# pidp11-io-expander.net
KiCad netlist of a schematic drawn in Altium Designer
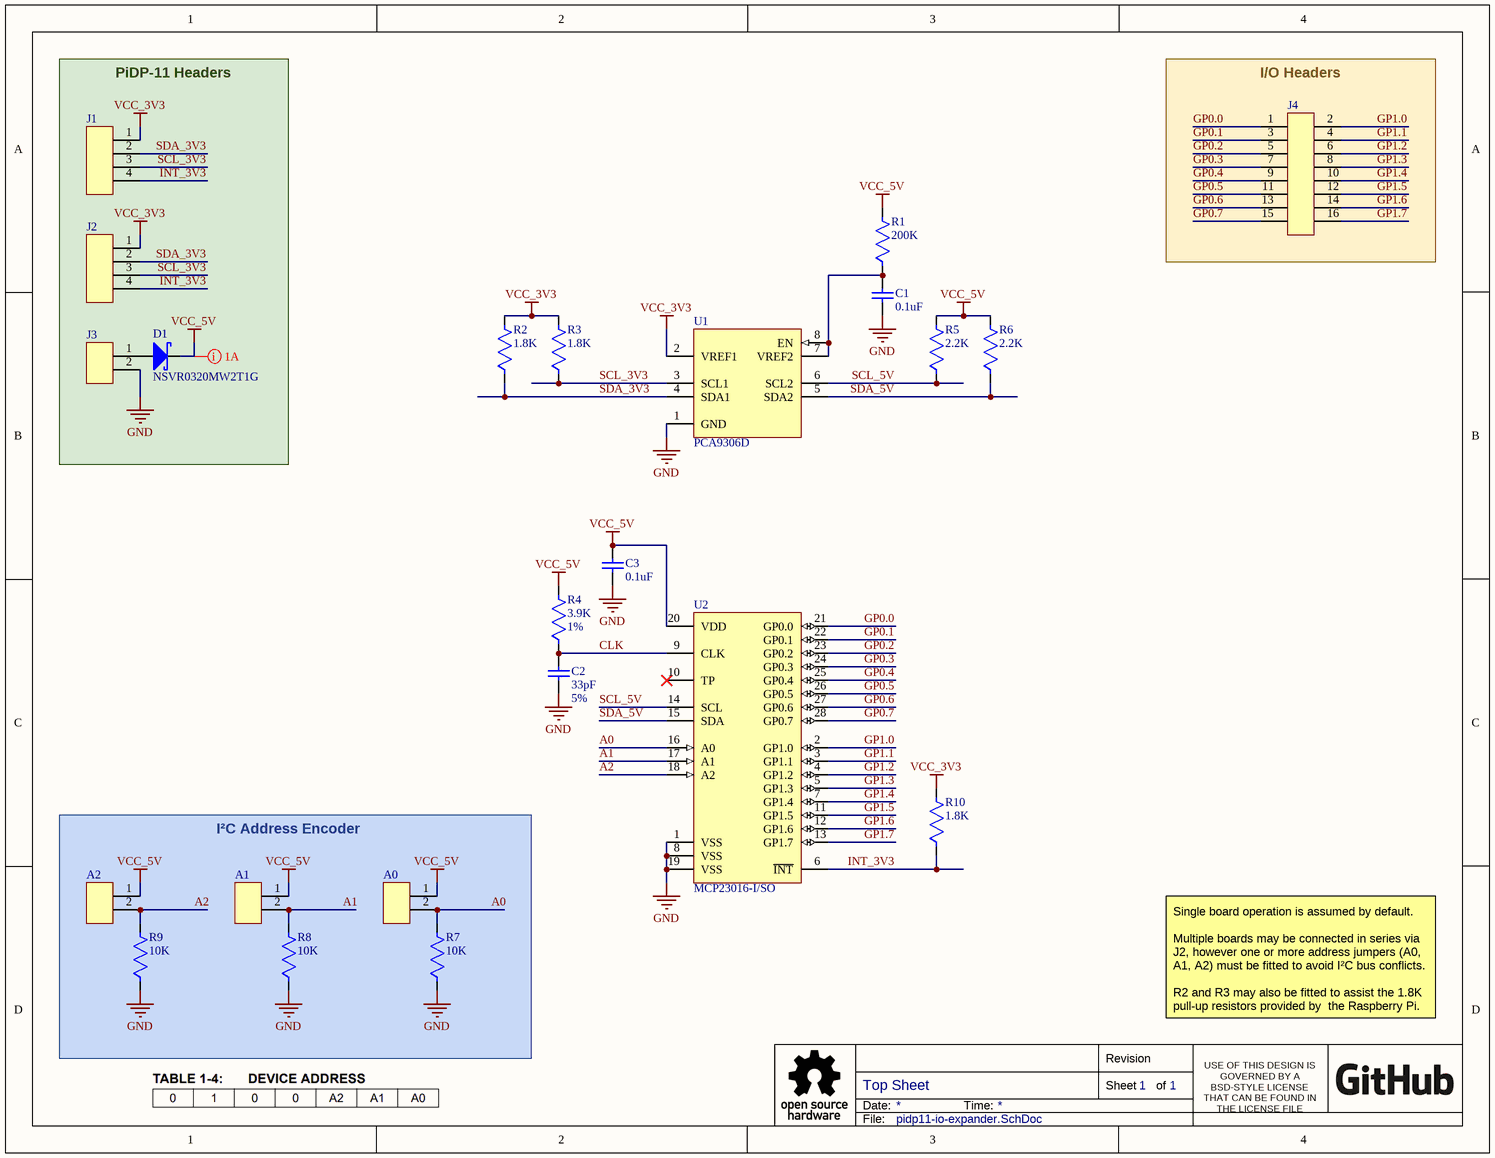
[diagram p0: pidp11-io-expander.SchDoc]

(export (version "E")
  (design (tool "Eeschema 10.0.6"))
  (components
    (comp (ref "A0")
      (value "10129378-902001BLF")
      (footprint "AMPH-10129378-902001BLF")
      (description "CONN HEADER VERT 2POS 2.54MM")
      (fields (field (name "MANUFACTURER") "Amphenol ICC"))
      (libsource (lib "Unified Components") (part "10129378-902001BLF"))
    )
    (comp (ref "A1")
      (value "10129378-902001BLF")
      (footprint "AMPH-10129378-902001BLF")
      (description "CONN HEADER VERT 2POS 2.54MM")
      (fields (field (name "MANUFACTURER") "Amphenol ICC"))
      (libsource (lib "Unified Components") (part "10129378-902001BLF"))
    )
    (comp (ref "A2")
      (value "10129378-902001BLF")
      (footprint "AMPH-10129378-902001BLF")
      (description "CONN HEADER VERT 2POS 2.54MM")
      (fields (field (name "MANUFACTURER") "Amphenol ICC"))
      (libsource (lib "Unified Components") (part "10129378-902001BLF"))
    )
    (comp (ref "C1")
      (value "0.1uF")
      (footprint "AVX-CC0402")
      (description "CAP CER 0.1UF 25V X7R 0402")
      (fields (field (name "MANUFACTURER PART NUMBER") "04023C104KAT2A") (field (name "MANUFACTURER") "AVX"))
      (libsource (lib "Unified Components") (part "04023C104KAT2A"))
    )
    (comp (ref "C2")
      (value "33pF")
      (footprint "AVX-CC0402")
      (description "CAP CER 33PF 25V C0G/NP0 0402")
      (fields
        (field (name "MANUFACTURER PART NUMBER") "04023A330JAT2A")
        (field (name "MANUFACTURER") "AVX")
        (field (name "TOLERANCE") "5%")
      )
      (libsource (lib "Unified Components") (part "04023A330JAT2A"))
    )
    (comp (ref "C3")
      (value "0.1uF")
      (footprint "AVX-CC0402")
      (description "CAP CER 0.1UF 25V X7R 0402")
      (fields (field (name "MANUFACTURER PART NUMBER") "04023C104KAT2A") (field (name "MANUFACTURER") "AVX"))
      (libsource (lib "Unified Components") (part "04023C104KAT2A"))
    )
    (comp (ref "D1")
      (value "NSVR0320MW2T1G")
      (footprint "ONSC-NSVR0320MW2T1G")
      (description "DIODE SCHOTTKY 20V 1A SOD323")
      (fields (field (name "MANUFACTURER") "ON Semiconductor"))
      (libsource (lib "Unified Components") (part "NSVR0320MW2T1G"))
    )
    (comp (ref "J1")
      (value "10129378-904001BLF")
      (footprint "AMPH-10129378-904001BLF")
      (description "CONN HEADER VERT 4POS 2.54MM")
      (fields (field (name "MANUFACTURER") "Amphenol ICC"))
      (libsource (lib "Unified Components") (part "10129378-904001BLF"))
    )
    (comp (ref "J2")
      (value "10129378-904001BLF")
      (footprint "AMPH-10129378-904001BLF")
      (description "CONN HEADER VERT 4POS 2.54MM")
      (fields (field (name "MANUFACTURER") "Amphenol ICC"))
      (libsource (lib "Unified Components") (part "10129378-904001BLF"))
    )
    (comp (ref "J3")
      (value "10129378-902001BLF")
      (footprint "AMPH-10129378-902001BLF")
      (description "CONN HEADER VERT 2POS 2.54MM")
      (fields (field (name "MANUFACTURER") "Amphenol ICC"))
      (libsource (lib "Unified Components") (part "10129378-902001BLF"))
    )
    (comp (ref "J4")
      (value "10129381-916001BLF")
      (footprint "AMPH-10129381-916001BLF")
      (description "CONN HEADER VERT 16POS 2.54MM")
      (fields (field (name "MANUFACTURER") "Amphenol ICC"))
      (libsource (lib "Unified Components") (part "10129381-916001BLF"))
    )
    (comp (ref "R1")
      (value "200K")
      (footprint "VBEY-CR0402")
      (description "RES SMD 200K OHM 1% 1/10W 0402")
      (fields
        (field (name "MANUFACTURER") "Vishay Beyschlag")
        (field (name "MANUFACTURER PART NUMBER") "MCS04020C2003FE000")
      )
      (libsource (lib "Unified Components") (part "MCS04020C2003FE000"))
    )
    (comp (ref "R2")
      (value "1.8K")
      (footprint "VBEY-CR0402")
      (description "RES SMD 1.8K OHM 1% 1/10W 0402")
      (fields
        (field (name "MANUFACTURER") "Vishay Beyschlag")
        (field (name "MANUFACTURER PART NUMBER") "MCS04020C1801FE000")
      )
      (libsource (lib "Unified Components") (part "MCS04020C1801FE000"))
    )
    (comp (ref "R3")
      (value "1.8K")
      (footprint "VBEY-CR0402")
      (description "RES SMD 1.8K OHM 1% 1/10W 0402")
      (fields
        (field (name "MANUFACTURER") "Vishay Beyschlag")
        (field (name "MANUFACTURER PART NUMBER") "MCS04020C1801FE000")
      )
      (libsource (lib "Unified Components") (part "MCS04020C1801FE000"))
    )
    (comp (ref "R4")
      (value "3.9K")
      (footprint "VBEY-CR0402")
      (description "RES SMD 3.9K OHM 1% 1/10W 0402")
      (fields
        (field (name "MANUFACTURER") "Vishay Beyschlag")
        (field (name "MANUFACTURER PART NUMBER") "MCS04020C3901FE000")
        (field (name "TOLERANCE") "1%")
      )
      (libsource (lib "Unified Components") (part "MCS04020C3901FE000"))
    )
    (comp (ref "R5")
      (value "2.2K")
      (footprint "VBEY-CR0402")
      (description "RES SMD 2.2K OHM 1% 1/10W 0402")
      (fields
        (field (name "MANUFACTURER") "Vishay Beyschlag")
        (field (name "MANUFACTURER PART NUMBER") "MCS04020C2201FE000")
      )
      (libsource (lib "Unified Components") (part "MCS04020C2201FE000"))
    )
    (comp (ref "R6")
      (value "2.2K")
      (footprint "VBEY-CR0402")
      (description "RES SMD 2.2K OHM 1% 1/10W 0402")
      (fields
        (field (name "MANUFACTURER") "Vishay Beyschlag")
        (field (name "MANUFACTURER PART NUMBER") "MCS04020C2201FE000")
      )
      (libsource (lib "Unified Components") (part "MCS04020C2201FE000"))
    )
    (comp (ref "R7")
      (value "10K")
      (footprint "VBEY-CR0402")
      (description "RES SMD 10K OHM 1% 1/10W 0402")
      (fields
        (field (name "MANUFACTURER") "Vishay Beyschlag")
        (field (name "MANUFACTURER PART NUMBER") "MCS0402MC1002FE000")
      )
      (libsource (lib "Unified Components") (part "MCS0402MC1002FE000"))
    )
    (comp (ref "R8")
      (value "10K")
      (footprint "VBEY-CR0402")
      (description "RES SMD 10K OHM 1% 1/10W 0402")
      (fields
        (field (name "MANUFACTURER") "Vishay Beyschlag")
        (field (name "MANUFACTURER PART NUMBER") "MCS0402MC1002FE000")
      )
      (libsource (lib "Unified Components") (part "MCS0402MC1002FE000"))
    )
    (comp (ref "R9")
      (value "10K")
      (footprint "VBEY-CR0402")
      (description "RES SMD 10K OHM 1% 1/10W 0402")
      (fields
        (field (name "MANUFACTURER") "Vishay Beyschlag")
        (field (name "MANUFACTURER PART NUMBER") "MCS0402MC1002FE000")
      )
      (libsource (lib "Unified Components") (part "MCS0402MC1002FE000"))
    )
    (comp (ref "R10")
      (value "1.8K")
      (footprint "VBEY-CR0402")
      (description "RES SMD 1.8K OHM 1% 1/10W 0402")
      (fields
        (field (name "MANUFACTURER") "Vishay Beyschlag")
        (field (name "MANUFACTURER PART NUMBER") "MCS04020C1801FE000")
      )
      (libsource (lib "Unified Components") (part "MCS04020C1801FE000"))
    )
    (comp (ref "U1")
      (value "PCA9306D")
      (footprint "NXP-PCA9306D")
      (description "IC TRNSLTR BIDIRECTIONAL 8SO")
      (fields (field (name "MANUFACTURER") "NXP"))
      (libsource (lib "Unified Components") (part "PCA9306D"))
    )
    (comp (ref "U2")
      (value "MCP23016-I/SO")
      (footprint "MCHP-SOIC-28")
      (description "IC I/O EXPANDER I2C 16B 28SOIC")
      (fields (field (name "MANUFACTURER") "Microchip"))
      (libsource (lib "Unified Components") (part "MCP23016-I/SO"))
    )
  )
  (nets
    (net (code "1") (name "/A0") (class "Default")
      (node (ref "A0") (pin "2") (pintype "open_emitter"))
      (node (ref "R7") (pin "2") (pinfunction "2_2") (pintype "passive"))
      (node (ref "U2") (pin "16") (pinfunction "A0_16") (pintype "input"))
    )
    (net (code "2") (name "/A1") (class "Default")
      (node (ref "A1") (pin "2") (pintype "open_emitter"))
      (node (ref "R8") (pin "2") (pinfunction "2_2") (pintype "passive"))
      (node (ref "U2") (pin "17") (pinfunction "A1_17") (pintype "input"))
    )
    (net (code "3") (name "/A2") (class "Default")
      (node (ref "A2") (pin "2") (pintype "open_emitter"))
      (node (ref "R9") (pin "2") (pinfunction "2_2") (pintype "passive"))
      (node (ref "U2") (pin "18") (pinfunction "A2_18") (pintype "input"))
    )
    (net (code "4") (name "/CLK") (class "Default")
      (node (ref "C2") (pin "1") (pinfunction "1_1") (pintype "passive"))
      (node (ref "R4") (pin "1") (pinfunction "1_1") (pintype "passive"))
      (node (ref "U2") (pin "9") (pinfunction "CLK_9") (pintype "passive"))
    )
    (net (code "5") (name "/GP0.0") (class "Default")
      (node (ref "J4") (pin "1") (pintype "passive"))
      (node (ref "U2") (pin "21") (pinfunction "GP0.0_21") (pintype "bidirectional"))
    )
    (net (code "6") (name "/GP0.1") (class "Default")
      (node (ref "J4") (pin "3") (pintype "passive"))
      (node (ref "U2") (pin "22") (pinfunction "GP0.1_22") (pintype "bidirectional"))
    )
    (net (code "7") (name "/GP0.2") (class "Default")
      (node (ref "J4") (pin "5") (pintype "passive"))
      (node (ref "U2") (pin "23") (pinfunction "GP0.2_23") (pintype "bidirectional"))
    )
    (net (code "8") (name "/GP0.3") (class "Default")
      (node (ref "J4") (pin "7") (pintype "passive"))
      (node (ref "U2") (pin "24") (pinfunction "GP0.3_24") (pintype "bidirectional"))
    )
    (net (code "9") (name "/GP0.4") (class "Default")
      (node (ref "J4") (pin "9") (pintype "passive"))
      (node (ref "U2") (pin "25") (pinfunction "GP0.4_25") (pintype "bidirectional"))
    )
    (net (code "10") (name "/GP0.5") (class "Default")
      (node (ref "J4") (pin "11") (pintype "passive"))
      (node (ref "U2") (pin "26") (pinfunction "GP0.5_26") (pintype "bidirectional"))
    )
    (net (code "11") (name "/GP0.6") (class "Default")
      (node (ref "J4") (pin "13") (pintype "passive"))
      (node (ref "U2") (pin "27") (pinfunction "GP0.6_27") (pintype "bidirectional"))
    )
    (net (code "12") (name "/GP0.7") (class "Default")
      (node (ref "J4") (pin "15") (pintype "passive"))
      (node (ref "U2") (pin "28") (pinfunction "GP0.7_28") (pintype "bidirectional"))
    )
    (net (code "13") (name "/GP1.0") (class "Default")
      (node (ref "J4") (pin "2") (pintype "passive"))
      (node (ref "U2") (pin "2") (pinfunction "GP1.0_2") (pintype "bidirectional"))
    )
    (net (code "14") (name "/GP1.1") (class "Default")
      (node (ref "J4") (pin "4") (pintype "passive"))
      (node (ref "U2") (pin "3") (pinfunction "GP1.1_3") (pintype "bidirectional"))
    )
    (net (code "15") (name "/GP1.2") (class "Default")
      (node (ref "J4") (pin "6") (pintype "passive"))
      (node (ref "U2") (pin "4") (pinfunction "GP1.2_4") (pintype "bidirectional"))
    )
    (net (code "16") (name "/GP1.3") (class "Default")
      (node (ref "J4") (pin "8") (pintype "passive"))
      (node (ref "U2") (pin "5") (pinfunction "GP1.3_5") (pintype "bidirectional"))
    )
    (net (code "17") (name "/GP1.4") (class "Default")
      (node (ref "J4") (pin "10") (pintype "passive"))
      (node (ref "U2") (pin "7") (pinfunction "GP1.4_7") (pintype "bidirectional"))
    )
    (net (code "18") (name "/GP1.5") (class "Default")
      (node (ref "J4") (pin "12") (pintype "passive"))
      (node (ref "U2") (pin "11") (pinfunction "GP1.5_11") (pintype "bidirectional"))
    )
    (net (code "19") (name "/GP1.6") (class "Default")
      (node (ref "J4") (pin "14") (pintype "passive"))
      (node (ref "U2") (pin "12") (pinfunction "GP1.6_12") (pintype "bidirectional"))
    )
    (net (code "20") (name "/GP1.7") (class "Default")
      (node (ref "J4") (pin "16") (pintype "passive"))
      (node (ref "U2") (pin "13") (pinfunction "GP1.7_13") (pintype "bidirectional"))
    )
    (net (code "21") (name "/INT_3V3") (class "Default")
      (node (ref "J1") (pin "4") (pintype "passive"))
      (node (ref "J2") (pin "4") (pintype "passive"))
      (node (ref "R10") (pin "1") (pinfunction "1_1") (pintype "passive"))
      (node (ref "U2") (pin "6") (pinfunction "INT_6") (pintype "open_collector"))
    )
    (net (code "22") (name "/SCL_3V3") (class "Default")
      (node (ref "J1") (pin "3") (pintype "passive"))
      (node (ref "J2") (pin "3") (pintype "passive"))
      (node (ref "R3") (pin "1") (pinfunction "1_1") (pintype "passive"))
      (node (ref "U1") (pin "3") (pinfunction "SCL1_3") (pintype "open_collector"))
    )
    (net (code "23") (name "/SCL_5V") (class "Default")
      (node (ref "R5") (pin "1") (pinfunction "1_1") (pintype "passive"))
      (node (ref "U1") (pin "6") (pinfunction "SCL2_6") (pintype "open_collector"))
      (node (ref "U2") (pin "14") (pinfunction "SCL_14") (pintype "open_collector"))
    )
    (net (code "24") (name "/SDA_3V3") (class "Default")
      (node (ref "J1") (pin "2") (pintype "passive"))
      (node (ref "J2") (pin "2") (pintype "passive"))
      (node (ref "R2") (pin "1") (pinfunction "1_1") (pintype "passive"))
      (node (ref "U1") (pin "4") (pinfunction "SDA1_4") (pintype "open_collector"))
    )
    (net (code "25") (name "/SDA_5V") (class "Default")
      (node (ref "R6") (pin "1") (pinfunction "1_1") (pintype "passive"))
      (node (ref "U1") (pin "5") (pinfunction "SDA2_5") (pintype "open_collector"))
      (node (ref "U2") (pin "15") (pinfunction "SDA_15") (pintype "open_collector"))
    )
    (net (code "26") (name "GND") (class "Default")
      (node (ref "C1") (pin "1") (pinfunction "1_1") (pintype "passive"))
      (node (ref "C2") (pin "2") (pinfunction "2_2") (pintype "passive"))
      (node (ref "C3") (pin "1") (pinfunction "1_1") (pintype "passive"))
      (node (ref "J3") (pin "2") (pintype "open_emitter"))
      (node (ref "R7") (pin "1") (pinfunction "1_1") (pintype "passive"))
      (node (ref "R8") (pin "1") (pinfunction "1_1") (pintype "passive"))
      (node (ref "R9") (pin "1") (pinfunction "1_1") (pintype "passive"))
      (node (ref "U1") (pin "1") (pinfunction "GND_1") (pintype "power_in"))
      (node (ref "U2") (pin "1") (pinfunction "VSS_1") (pintype "power_in"))
      (node (ref "U2") (pin "19") (pinfunction "VSS_19") (pintype "power_in"))
      (node (ref "U2") (pin "8") (pinfunction "VSS_8") (pintype "power_in"))
    )
    (net (code "27") (name "Net-(D1-PadA)") (class "Default")
      (node (ref "D1") (pin "A") (pinfunction "A_A") (pintype "passive"))
      (node (ref "J3") (pin "1") (pintype "passive"))
    )
    (net (code "28") (name "Net-(U1-EN)") (class "Default")
      (node (ref "C1") (pin "2") (pinfunction "2_2") (pintype "passive"))
      (node (ref "R1") (pin "1") (pinfunction "1_1") (pintype "passive"))
      (node (ref "U1") (pin "7") (pinfunction "VREF2_7") (pintype "power_in"))
      (node (ref "U1") (pin "8") (pinfunction "EN_8") (pintype "input"))
    )
    (net (code "29") (name "VCC_3V3") (class "Default")
      (node (ref "J1") (pin "1") (pintype "passive"))
      (node (ref "J2") (pin "1") (pintype "passive"))
      (node (ref "R10") (pin "2") (pinfunction "2_2") (pintype "passive"))
      (node (ref "R2") (pin "2") (pinfunction "2_2") (pintype "passive"))
      (node (ref "R3") (pin "2") (pinfunction "2_2") (pintype "passive"))
      (node (ref "U1") (pin "2") (pinfunction "VREF1_2") (pintype "power_in"))
    )
    (net (code "30") (name "VCC_5V") (class "Default")
      (node (ref "A0") (pin "1") (pintype "passive"))
      (node (ref "A1") (pin "1") (pintype "passive"))
      (node (ref "A2") (pin "1") (pintype "passive"))
      (node (ref "C3") (pin "2") (pinfunction "2_2") (pintype "passive"))
      (node (ref "D1") (pin "C") (pinfunction "C_C") (pintype "passive"))
      (node (ref "R1") (pin "2") (pinfunction "2_2") (pintype "passive"))
      (node (ref "R4") (pin "2") (pinfunction "2_2") (pintype "passive"))
      (node (ref "R5") (pin "2") (pinfunction "2_2") (pintype "passive"))
      (node (ref "R6") (pin "2") (pinfunction "2_2") (pintype "passive"))
      (node (ref "U2") (pin "20") (pinfunction "VDD_20") (pintype "power_in"))
    )
    (net (code "31") (name "unconnected-(U2-TP-Pad10)") (class "Default")
      (node (ref "U2") (pin "10") (pinfunction "TP_10") (pintype "passive+no_connect"))
    )
  )
)
